# motorconnect.net
KiCad netlist of a schematic drawn in EAGLE
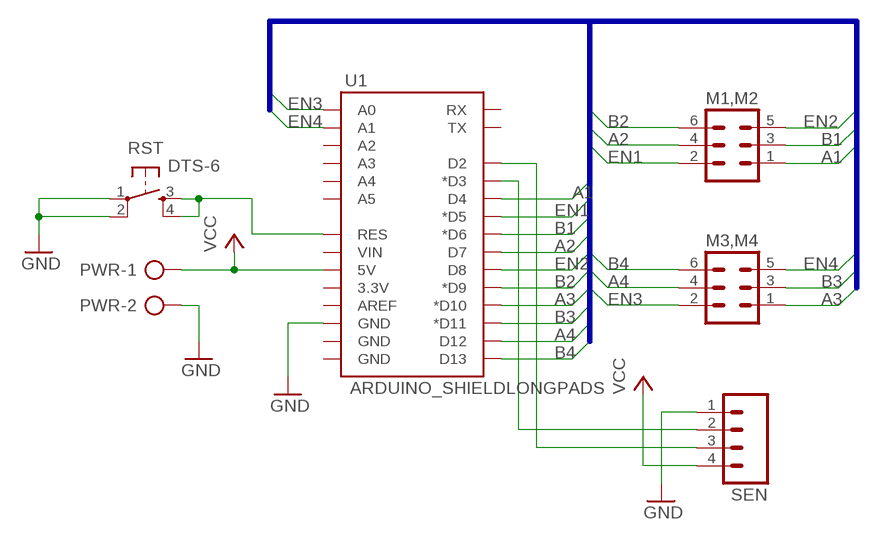
[diagram p0: schematic, sheet 1]

(export (version "E")
  (design (tool "Eeschema 10.0.6"))
  (components
    (comp (ref "M1,M2")
      (value "ML6")
      (footprint "eagle-import:ML6")
      (libsource (lib "eagle-import") (part "ML6"))
    )
    (comp (ref "M3,M4")
      (value "ML6")
      (footprint "eagle-import:ML6")
      (libsource (lib "eagle-import") (part "ML6"))
    )
    (comp (ref "PWR")
      (value "AK500/2")
      (footprint "eagle-import:AK500_2")
      (libsource (lib "eagle-import") (part "AK500/2"))
    )
    (comp (ref "RST")
      (value "DTS-6")
      (footprint "eagle-import:DTS-6")
      (libsource (lib "eagle-import") (part "DTS-6"))
    )
    (comp (ref "SEN")
      (value "M04LONGPADS")
      (footprint "eagle-import:1X04_LONGPADS")
      (libsource (lib "eagle-import") (part "M04LONGPADS"))
    )
    (comp (ref "U1")
      (value "ARDUINO_SHIELDLONGPADS")
      (footprint "eagle-import:DUEMILANOVE_SHIELD_LONGPADS")
      (libsource (lib "eagle-import") (part "ARDUINO_SHIELDLONGPADS"))
    )
  )
  (nets
    (net (code "1") (name "/A1") (class "Default")
      (node (ref "M1,M2") (pin "1") (pinfunction "1_1") (pintype "passive"))
      (node (ref "U1") (pin "D4") (pinfunction "D4_D4") (pintype "bidirectional"))
    )
    (net (code "2") (name "/A2") (class "Default")
      (node (ref "M1,M2") (pin "4") (pinfunction "4_4") (pintype "passive"))
      (node (ref "U1") (pin "D7") (pinfunction "D7_D7") (pintype "bidirectional"))
    )
    (net (code "3") (name "/A3") (class "Default")
      (node (ref "M3,M4") (pin "1") (pinfunction "1_1") (pintype "passive"))
      (node (ref "U1") (pin "D10") (pinfunction "*D10_D10") (pintype "bidirectional"))
    )
    (net (code "4") (name "/A4") (class "Default")
      (node (ref "M3,M4") (pin "4") (pinfunction "4_4") (pintype "passive"))
      (node (ref "U1") (pin "D12") (pinfunction "D12_D12") (pintype "bidirectional"))
    )
    (net (code "5") (name "/B1") (class "Default")
      (node (ref "M1,M2") (pin "3") (pinfunction "3_3") (pintype "passive"))
      (node (ref "U1") (pin "D6") (pinfunction "*D6_D6") (pintype "bidirectional"))
    )
    (net (code "6") (name "/B2") (class "Default")
      (node (ref "M1,M2") (pin "6") (pinfunction "6_6") (pintype "passive"))
      (node (ref "U1") (pin "D9") (pinfunction "*D9_D9") (pintype "bidirectional"))
    )
    (net (code "7") (name "/B3") (class "Default")
      (node (ref "M3,M4") (pin "3") (pinfunction "3_3") (pintype "passive"))
      (node (ref "U1") (pin "D11") (pinfunction "*D11_D11") (pintype "bidirectional"))
    )
    (net (code "8") (name "/B4") (class "Default")
      (node (ref "M3,M4") (pin "6") (pinfunction "6_6") (pintype "passive"))
      (node (ref "U1") (pin "D13") (pinfunction "D13_D13") (pintype "bidirectional"))
    )
    (net (code "9") (name "/EN1") (class "Default")
      (node (ref "M1,M2") (pin "2") (pinfunction "2_2") (pintype "passive"))
      (node (ref "U1") (pin "D5") (pinfunction "*D5_D5") (pintype "bidirectional"))
    )
    (net (code "10") (name "/EN2") (class "Default")
      (node (ref "M1,M2") (pin "5") (pinfunction "5_5") (pintype "passive"))
      (node (ref "U1") (pin "D8") (pinfunction "D8_D8") (pintype "bidirectional"))
    )
    (net (code "11") (name "/EN3") (class "Default")
      (node (ref "M3,M4") (pin "2") (pinfunction "2_2") (pintype "passive"))
      (node (ref "U1") (pin "A0") (pinfunction "A0_A0") (pintype "bidirectional"))
    )
    (net (code "12") (name "/EN4") (class "Default")
      (node (ref "M3,M4") (pin "5") (pinfunction "5_5") (pintype "passive"))
      (node (ref "U1") (pin "A1") (pinfunction "A1_A1") (pintype "bidirectional"))
    )
    (net (code "13") (name "GND") (class "Default")
      (node (ref "PWR") (pin "2") (pinfunction "KL_2") (pintype "passive"))
      (node (ref "RST") (pin "1") (pinfunction "1_1") (pintype "passive"))
      (node (ref "RST") (pin "2") (pinfunction "2_2") (pintype "passive"))
      (node (ref "SEN") (pin "1") (pinfunction "1_1") (pintype "passive"))
      (node (ref "U1") (pin "GND@2") (pinfunction "GND_GND@2") (pintype "bidirectional"))
    )
    (net (code "14") (name "Net-(RST-Pad3)") (class "Default")
      (node (ref "RST") (pin "3") (pinfunction "3_3") (pintype "passive"))
      (node (ref "RST") (pin "4") (pinfunction "4_4") (pintype "passive"))
      (node (ref "U1") (pin "RES") (pinfunction "RES_RES") (pintype "bidirectional"))
    )
    (net (code "15") (name "Net-(SEN-Pad3)") (class "Default")
      (node (ref "SEN") (pin "3") (pinfunction "3_3") (pintype "passive"))
      (node (ref "U1") (pin "D2") (pinfunction "D2_D2") (pintype "bidirectional"))
    )
    (net (code "16") (name "Net-(U1-*D3)") (class "Default")
      (node (ref "SEN") (pin "2") (pinfunction "2_2") (pintype "passive"))
      (node (ref "U1") (pin "D3") (pinfunction "*D3_D3") (pintype "bidirectional"))
    )
    (net (code "17") (name "VCC") (class "Default")
      (node (ref "PWR") (pin "1") (pinfunction "KL_1") (pintype "passive"))
      (node (ref "SEN") (pin "4") (pinfunction "4_4") (pintype "passive"))
      (node (ref "U1") (pin "5V") (pinfunction "5V_5V") (pintype "bidirectional"))
    )
    (net (code "18") (name "unconnected-(U1-GND-PadGND@0)") (class "Default")
      (node (ref "U1") (pin "GND@0") (pinfunction "GND_GND@0") (pintype "bidirectional"))
    )
    (net (code "19") (name "unconnected-(U1-GND-PadGND@1)") (class "Default")
      (node (ref "U1") (pin "GND@1") (pinfunction "GND_GND@1") (pintype "bidirectional"))
    )
    (net (code "20") (name "unconnected-(U1-Pad3.3V)") (class "Default")
      (node (ref "U1") (pin "3.3V") (pinfunction "3.3V_3.3V") (pintype "bidirectional"))
    )
    (net (code "21") (name "unconnected-(U1-PadA2)") (class "Default")
      (node (ref "U1") (pin "A2") (pinfunction "A2_A2") (pintype "bidirectional"))
    )
    (net (code "22") (name "unconnected-(U1-PadA3)") (class "Default")
      (node (ref "U1") (pin "A3") (pinfunction "A3_A3") (pintype "bidirectional"))
    )
    (net (code "23") (name "unconnected-(U1-PadA4)") (class "Default")
      (node (ref "U1") (pin "A4") (pinfunction "A4_A4") (pintype "bidirectional"))
    )
    (net (code "24") (name "unconnected-(U1-PadA5)") (class "Default")
      (node (ref "U1") (pin "A5") (pinfunction "A5_A5") (pintype "bidirectional"))
    )
    (net (code "25") (name "unconnected-(U1-PadAREF)") (class "Default")
      (node (ref "U1") (pin "AREF") (pinfunction "AREF_AREF") (pintype "bidirectional"))
    )
    (net (code "26") (name "unconnected-(U1-PadRX)") (class "Default")
      (node (ref "U1") (pin "RX") (pinfunction "RX_RX") (pintype "bidirectional"))
    )
    (net (code "27") (name "unconnected-(U1-PadTX)") (class "Default")
      (node (ref "U1") (pin "TX") (pinfunction "TX_TX") (pintype "bidirectional"))
    )
    (net (code "28") (name "unconnected-(U1-PadVIN)") (class "Default")
      (node (ref "U1") (pin "VIN") (pinfunction "VIN_VIN") (pintype "bidirectional"))
    )
  )
)
